# ESP_rgb_led_server_revA.net
KiCad netlist of a schematic drawn in EAGLE
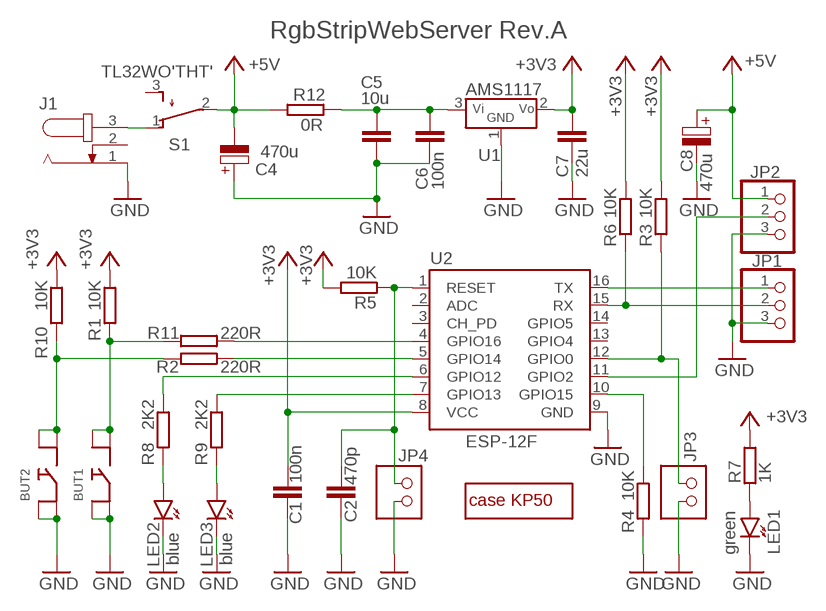
[diagram p0: schematic, sheet 1]

(export (version "E")
  (design (tool "Eeschema 10.0.6"))
  (components
    (comp (ref "BUT1")
      (value "BUTTON'SMD'")
      (footprint "eagle-import:BUTTON_SMD")
      (libsource (lib "eagle-import") (part "BUTTON'SMD'"))
    )
    (comp (ref "BUT2")
      (value "BUTTON'SMD'")
      (footprint "eagle-import:BUTTON_SMD")
      (libsource (lib "eagle-import") (part "BUTTON'SMD'"))
    )
    (comp (ref "C1")
      (value "100n")
      (footprint "eagle-import:C0805")
      (libsource (lib "eagle-import") (part "C-CERAMIC'SMD'"))
    )
    (comp (ref "C2")
      (value "470p")
      (footprint "eagle-import:C0805")
      (libsource (lib "eagle-import") (part "C-CERAMIC'SMD'"))
    )
    (comp (ref "C4")
      (value "470u")
      (footprint "eagle-import:ELYT-10MM_90")
      (libsource (lib "eagle-import") (part "C-POLY'10MM/90'"))
    )
    (comp (ref "C5")
      (value "10u")
      (footprint "eagle-import:C0805")
      (libsource (lib "eagle-import") (part "C-CERAMIC'SMD'"))
    )
    (comp (ref "C6")
      (value "100n")
      (footprint "eagle-import:C0805")
      (libsource (lib "eagle-import") (part "C-CERAMIC'SMD'"))
    )
    (comp (ref "C7")
      (value "22u")
      (footprint "eagle-import:C0805")
      (libsource (lib "eagle-import") (part "C-CERAMIC'SMD'"))
    )
    (comp (ref "C8")
      (value "470u")
      (footprint "eagle-import:ELYT-10MM_90")
      (libsource (lib "eagle-import") (part "C-POLY'10MM/90'"))
    )
    (comp (ref "J1")
      (value "JACK-PLUG1")
      (footprint "eagle-import:SPC4078")
      (libsource (lib "eagle-import") (part "JACK-PLUG1"))
    )
    (comp (ref "JP1")
      (value "PINHD-3X1")
      (footprint "eagle-import:PINHD-3X1")
      (libsource (lib "eagle-import") (part "PINHD-3X1"))
    )
    (comp (ref "JP2")
      (value "PINHD-3X1")
      (footprint "eagle-import:PINHD-3X1")
      (libsource (lib "eagle-import") (part "PINHD-3X1"))
    )
    (comp (ref "JP3")
      (value "PINHD-2X1")
      (footprint "eagle-import:PINHD-2X1")
      (libsource (lib "eagle-import") (part "PINHD-2X1"))
    )
    (comp (ref "JP4")
      (value "PINHD-2X1")
      (footprint "eagle-import:PINHD-2X1")
      (libsource (lib "eagle-import") (part "PINHD-2X1"))
    )
    (comp (ref "LED1")
      (value "green")
      (footprint "eagle-import:LED3MM")
      (libsource (lib "eagle-import") (part "LED'3MM'"))
    )
    (comp (ref "LED2")
      (value "blue")
      (footprint "eagle-import:LED3MM")
      (libsource (lib "eagle-import") (part "LED'3MM'"))
    )
    (comp (ref "LED3")
      (value "blue")
      (footprint "eagle-import:LED3MM")
      (libsource (lib "eagle-import") (part "LED'3MM'"))
    )
    (comp (ref "R1")
      (value "10K")
      (footprint "eagle-import:R0805")
      (libsource (lib "eagle-import") (part "R'2'"))
    )
    (comp (ref "R2")
      (value "220R")
      (footprint "eagle-import:R0805")
      (libsource (lib "eagle-import") (part "R'2'"))
    )
    (comp (ref "R3")
      (value "10K")
      (footprint "eagle-import:R0805")
      (libsource (lib "eagle-import") (part "R'2'"))
    )
    (comp (ref "R4")
      (value "10K")
      (footprint "eagle-import:R0805")
      (libsource (lib "eagle-import") (part "R'2'"))
    )
    (comp (ref "R5")
      (value "10K")
      (footprint "eagle-import:R0805")
      (libsource (lib "eagle-import") (part "R'2'"))
    )
    (comp (ref "R6")
      (value "10K")
      (footprint "eagle-import:R0805")
      (libsource (lib "eagle-import") (part "R'2'"))
    )
    (comp (ref "R7")
      (value "1K")
      (footprint "eagle-import:R0805")
      (libsource (lib "eagle-import") (part "R'2'"))
    )
    (comp (ref "R8")
      (value "2K2")
      (footprint "eagle-import:R0805")
      (libsource (lib "eagle-import") (part "R'2'"))
    )
    (comp (ref "R9")
      (value "2K2")
      (footprint "eagle-import:R0805")
      (libsource (lib "eagle-import") (part "R'2'"))
    )
    (comp (ref "R10")
      (value "10K")
      (footprint "eagle-import:R0805")
      (libsource (lib "eagle-import") (part "R'2'"))
    )
    (comp (ref "R11")
      (value "220R")
      (footprint "eagle-import:R0805")
      (libsource (lib "eagle-import") (part "R'2'"))
    )
    (comp (ref "R12")
      (value "0R")
      (footprint "eagle-import:R0805")
      (libsource (lib "eagle-import") (part "R'2'"))
    )
    (comp (ref "S1")
      (value "TL32WO'THT'")
      (footprint "eagle-import:TL3XWO")
      (libsource (lib "eagle-import") (part "TL32WO'THT'"))
    )
    (comp (ref "U$1")
      (value "CASE-KP50")
      (footprint "eagle-import:KP50-CASE")
      (libsource (lib "eagle-import") (part "CASE-KP50"))
    )
    (comp (ref "U1")
      (value "AMS1117")
      (footprint "eagle-import:SOT223")
      (libsource (lib "eagle-import") (part "V_STAB'TS1117'"))
    )
    (comp (ref "U2")
      (value "ESP-12F")
      (footprint "eagle-import:ESP-12F-ADAPTER")
      (libsource (lib "eagle-import") (part "ESP-12F"))
    )
  )
  (nets
    (net (code "1") (name "+3V3") (class "Default")
      (node (ref "C1") (pin "2") (pinfunction "P$2_2") (pintype "bidirectional"))
      (node (ref "C7") (pin "2") (pinfunction "P$2_2") (pintype "bidirectional"))
      (node (ref "R1") (pin "2") (pinfunction "P$2_2") (pintype "bidirectional"))
      (node (ref "R10") (pin "2") (pinfunction "P$2_2") (pintype "bidirectional"))
      (node (ref "R3") (pin "2") (pinfunction "P$2_2") (pintype "bidirectional"))
      (node (ref "R5") (pin "2") (pinfunction "P$2_2") (pintype "bidirectional"))
      (node (ref "R6") (pin "2") (pinfunction "P$2_2") (pintype "bidirectional"))
      (node (ref "R7") (pin "2") (pinfunction "P$2_2") (pintype "bidirectional"))
      (node (ref "U1") (pin "2") (pinfunction "VOUT_2") (pintype "power_in"))
      (node (ref "U2") (pin "8") (pinfunction "VCC_8") (pintype "power_in"))
    )
    (net (code "2") (name "+5V") (class "Default")
      (node (ref "C4") (pin "N") (pinfunction "NEG_N") (pintype "bidirectional"))
      (node (ref "C8") (pin "P") (pinfunction "POS_P") (pintype "bidirectional"))
      (node (ref "JP2") (pin "1") (pinfunction "1_1") (pintype "passive"))
      (node (ref "R12") (pin "2") (pinfunction "P$2_2") (pintype "bidirectional"))
      (node (ref "S1") (pin "2") (pinfunction "P_2") (pintype "passive"))
    )
    (net (code "3") (name "GND") (class "Default")
      (node (ref "BUT1") (pin "1") (pinfunction "4_1") (pintype "bidirectional"))
      (node (ref "BUT1") (pin "2") (pinfunction "2_2") (pintype "bidirectional"))
      (node (ref "BUT2") (pin "1") (pinfunction "4_1") (pintype "bidirectional"))
      (node (ref "BUT2") (pin "2") (pinfunction "2_2") (pintype "bidirectional"))
      (node (ref "C1") (pin "1") (pinfunction "P$1_1") (pintype "bidirectional"))
      (node (ref "C2") (pin "1") (pinfunction "P$1_1") (pintype "bidirectional"))
      (node (ref "C4") (pin "P") (pinfunction "POS_P") (pintype "bidirectional"))
      (node (ref "C5") (pin "1") (pinfunction "P$1_1") (pintype "bidirectional"))
      (node (ref "C6") (pin "1") (pinfunction "P$1_1") (pintype "bidirectional"))
      (node (ref "C7") (pin "1") (pinfunction "P$1_1") (pintype "bidirectional"))
      (node (ref "C8") (pin "N") (pinfunction "NEG_N") (pintype "bidirectional"))
      (node (ref "J1") (pin "1") (pinfunction "1_1") (pintype "passive"))
      (node (ref "JP1") (pin "3") (pinfunction "3_3") (pintype "passive"))
      (node (ref "JP2") (pin "3") (pinfunction "3_3") (pintype "passive"))
      (node (ref "JP3") (pin "2") (pinfunction "2_2") (pintype "bidirectional"))
      (node (ref "JP4") (pin "2") (pinfunction "2_2") (pintype "bidirectional"))
      (node (ref "LED1") (pin "K") (pinfunction "K_K") (pintype "bidirectional"))
      (node (ref "LED2") (pin "K") (pinfunction "K_K") (pintype "bidirectional"))
      (node (ref "LED3") (pin "K") (pinfunction "K_K") (pintype "bidirectional"))
      (node (ref "R4") (pin "1") (pinfunction "P$1_1") (pintype "bidirectional"))
      (node (ref "U1") (pin "1") (pinfunction "GND_1") (pintype "power_in"))
      (node (ref "U2") (pin "9") (pinfunction "GND_9") (pintype "power_in"))
    )
    (net (code "4") (name "Net-(BUT1-1)") (class "Default")
      (node (ref "BUT1") (pin "3") (pinfunction "1_3") (pintype "bidirectional"))
      (node (ref "BUT1") (pin "4") (pinfunction "3_4") (pintype "bidirectional"))
      (node (ref "R1") (pin "1") (pinfunction "P$1_1") (pintype "bidirectional"))
      (node (ref "R11") (pin "1") (pinfunction "P$1_1") (pintype "bidirectional"))
    )
    (net (code "5") (name "Net-(BUT2-1)") (class "Default")
      (node (ref "BUT2") (pin "3") (pinfunction "1_3") (pintype "bidirectional"))
      (node (ref "BUT2") (pin "4") (pinfunction "3_4") (pintype "bidirectional"))
      (node (ref "R10") (pin "1") (pinfunction "P$1_1") (pintype "bidirectional"))
      (node (ref "R2") (pin "1") (pinfunction "P$1_1") (pintype "bidirectional"))
    )
    (net (code "6") (name "Net-(C2-P$2)") (class "Default")
      (node (ref "C2") (pin "2") (pinfunction "P$2_2") (pintype "bidirectional"))
      (node (ref "JP4") (pin "1") (pinfunction "1_1") (pintype "input"))
      (node (ref "R5") (pin "1") (pinfunction "P$1_1") (pintype "bidirectional"))
      (node (ref "U2") (pin "1") (pinfunction "RESET_1") (pintype "bidirectional"))
    )
    (net (code "7") (name "Net-(C5-P$2)") (class "Default")
      (node (ref "C5") (pin "2") (pinfunction "P$2_2") (pintype "bidirectional"))
      (node (ref "C6") (pin "2") (pinfunction "P$2_2") (pintype "bidirectional"))
      (node (ref "R12") (pin "1") (pinfunction "P$1_1") (pintype "bidirectional"))
      (node (ref "U1") (pin "3") (pinfunction "VIN_3") (pintype "power_in"))
    )
    (net (code "8") (name "Net-(R2-P$2)") (class "Default")
      (node (ref "R2") (pin "2") (pinfunction "P$2_2") (pintype "bidirectional"))
      (node (ref "U2") (pin "5") (pinfunction "GPIO14_5") (pintype "bidirectional"))
    )
    (net (code "9") (name "Net-(R3-P$1)") (class "Default")
      (node (ref "JP3") (pin "1") (pinfunction "1_1") (pintype "input"))
      (node (ref "R3") (pin "1") (pinfunction "P$1_1") (pintype "bidirectional"))
      (node (ref "U2") (pin "12") (pinfunction "GPIO0_12") (pintype "bidirectional"))
    )
    (net (code "10") (name "Net-(R4-P$2)") (class "Default")
      (node (ref "R4") (pin "2") (pinfunction "P$2_2") (pintype "bidirectional"))
      (node (ref "U2") (pin "10") (pinfunction "GPIO15_10") (pintype "bidirectional"))
    )
    (net (code "11") (name "Net-(R6-P$1)") (class "Default")
      (node (ref "JP1") (pin "2") (pinfunction "2_2") (pintype "passive"))
      (node (ref "R6") (pin "1") (pinfunction "P$1_1") (pintype "bidirectional"))
      (node (ref "U2") (pin "15") (pinfunction "RX_15") (pintype "bidirectional"))
    )
    (net (code "12") (name "Net-(R7-P$1)") (class "Default")
      (node (ref "LED1") (pin "A") (pinfunction "A_A") (pintype "bidirectional"))
      (node (ref "R7") (pin "1") (pinfunction "P$1_1") (pintype "bidirectional"))
    )
    (net (code "13") (name "Net-(R8-P$1)") (class "Default")
      (node (ref "LED2") (pin "A") (pinfunction "A_A") (pintype "bidirectional"))
      (node (ref "R8") (pin "1") (pinfunction "P$1_1") (pintype "bidirectional"))
    )
    (net (code "14") (name "Net-(R8-P$2)") (class "Default")
      (node (ref "R8") (pin "2") (pinfunction "P$2_2") (pintype "bidirectional"))
      (node (ref "U2") (pin "6") (pinfunction "GPIO12_6") (pintype "bidirectional"))
    )
    (net (code "15") (name "Net-(R9-P$1)") (class "Default")
      (node (ref "LED3") (pin "A") (pinfunction "A_A") (pintype "bidirectional"))
      (node (ref "R9") (pin "1") (pinfunction "P$1_1") (pintype "bidirectional"))
    )
    (net (code "16") (name "Net-(R9-P$2)") (class "Default")
      (node (ref "R9") (pin "2") (pinfunction "P$2_2") (pintype "bidirectional"))
      (node (ref "U2") (pin "7") (pinfunction "GPIO13_7") (pintype "bidirectional"))
    )
    (net (code "17") (name "Net-(R11-P$2)") (class "Default")
      (node (ref "R11") (pin "2") (pinfunction "P$2_2") (pintype "bidirectional"))
      (node (ref "U2") (pin "4") (pinfunction "GPIO16_4") (pintype "bidirectional"))
    )
    (net (code "18") (name "Net-(S1-O)") (class "Default")
      (node (ref "J1") (pin "3") (pinfunction "3_3") (pintype "passive"))
      (node (ref "S1") (pin "1") (pinfunction "O_1") (pintype "passive"))
    )
    (net (code "19") (name "Net-(U2-GPIO2)") (class "Default")
      (node (ref "JP2") (pin "2") (pinfunction "2_2") (pintype "passive"))
      (node (ref "U2") (pin "11") (pinfunction "GPIO2_11") (pintype "bidirectional"))
    )
    (net (code "20") (name "Net-(U2-TX)") (class "Default")
      (node (ref "JP1") (pin "1") (pinfunction "1_1") (pintype "passive"))
      (node (ref "U2") (pin "16") (pinfunction "TX_16") (pintype "bidirectional"))
    )
    (net (code "21") (name "unconnected-(J1-Pad2)") (class "Default")
      (node (ref "J1") (pin "2") (pinfunction "2_2") (pintype "passive"))
    )
    (net (code "22") (name "unconnected-(S1-S-Pad3)") (class "Default")
      (node (ref "S1") (pin "3") (pinfunction "S_3") (pintype "passive"))
    )
    (net (code "23") (name "unconnected-(U2-ADC-Pad2)") (class "Default")
      (node (ref "U2") (pin "2") (pinfunction "ADC_2") (pintype "bidirectional"))
    )
    (net (code "24") (name "unconnected-(U2-CH_PD-Pad3)") (class "Default")
      (node (ref "U2") (pin "3") (pinfunction "CH_PD_3") (pintype "bidirectional"))
    )
    (net (code "25") (name "unconnected-(U2-GPIO4-Pad13)") (class "Default")
      (node (ref "U2") (pin "13") (pinfunction "GPIO4_13") (pintype "bidirectional"))
    )
    (net (code "26") (name "unconnected-(U2-GPIO5-Pad14)") (class "Default")
      (node (ref "U2") (pin "14") (pinfunction "GPIO5_14") (pintype "bidirectional"))
    )
  )
)
